# Power_Supply.net
KiCad netlist of a schematic drawn in EAGLE
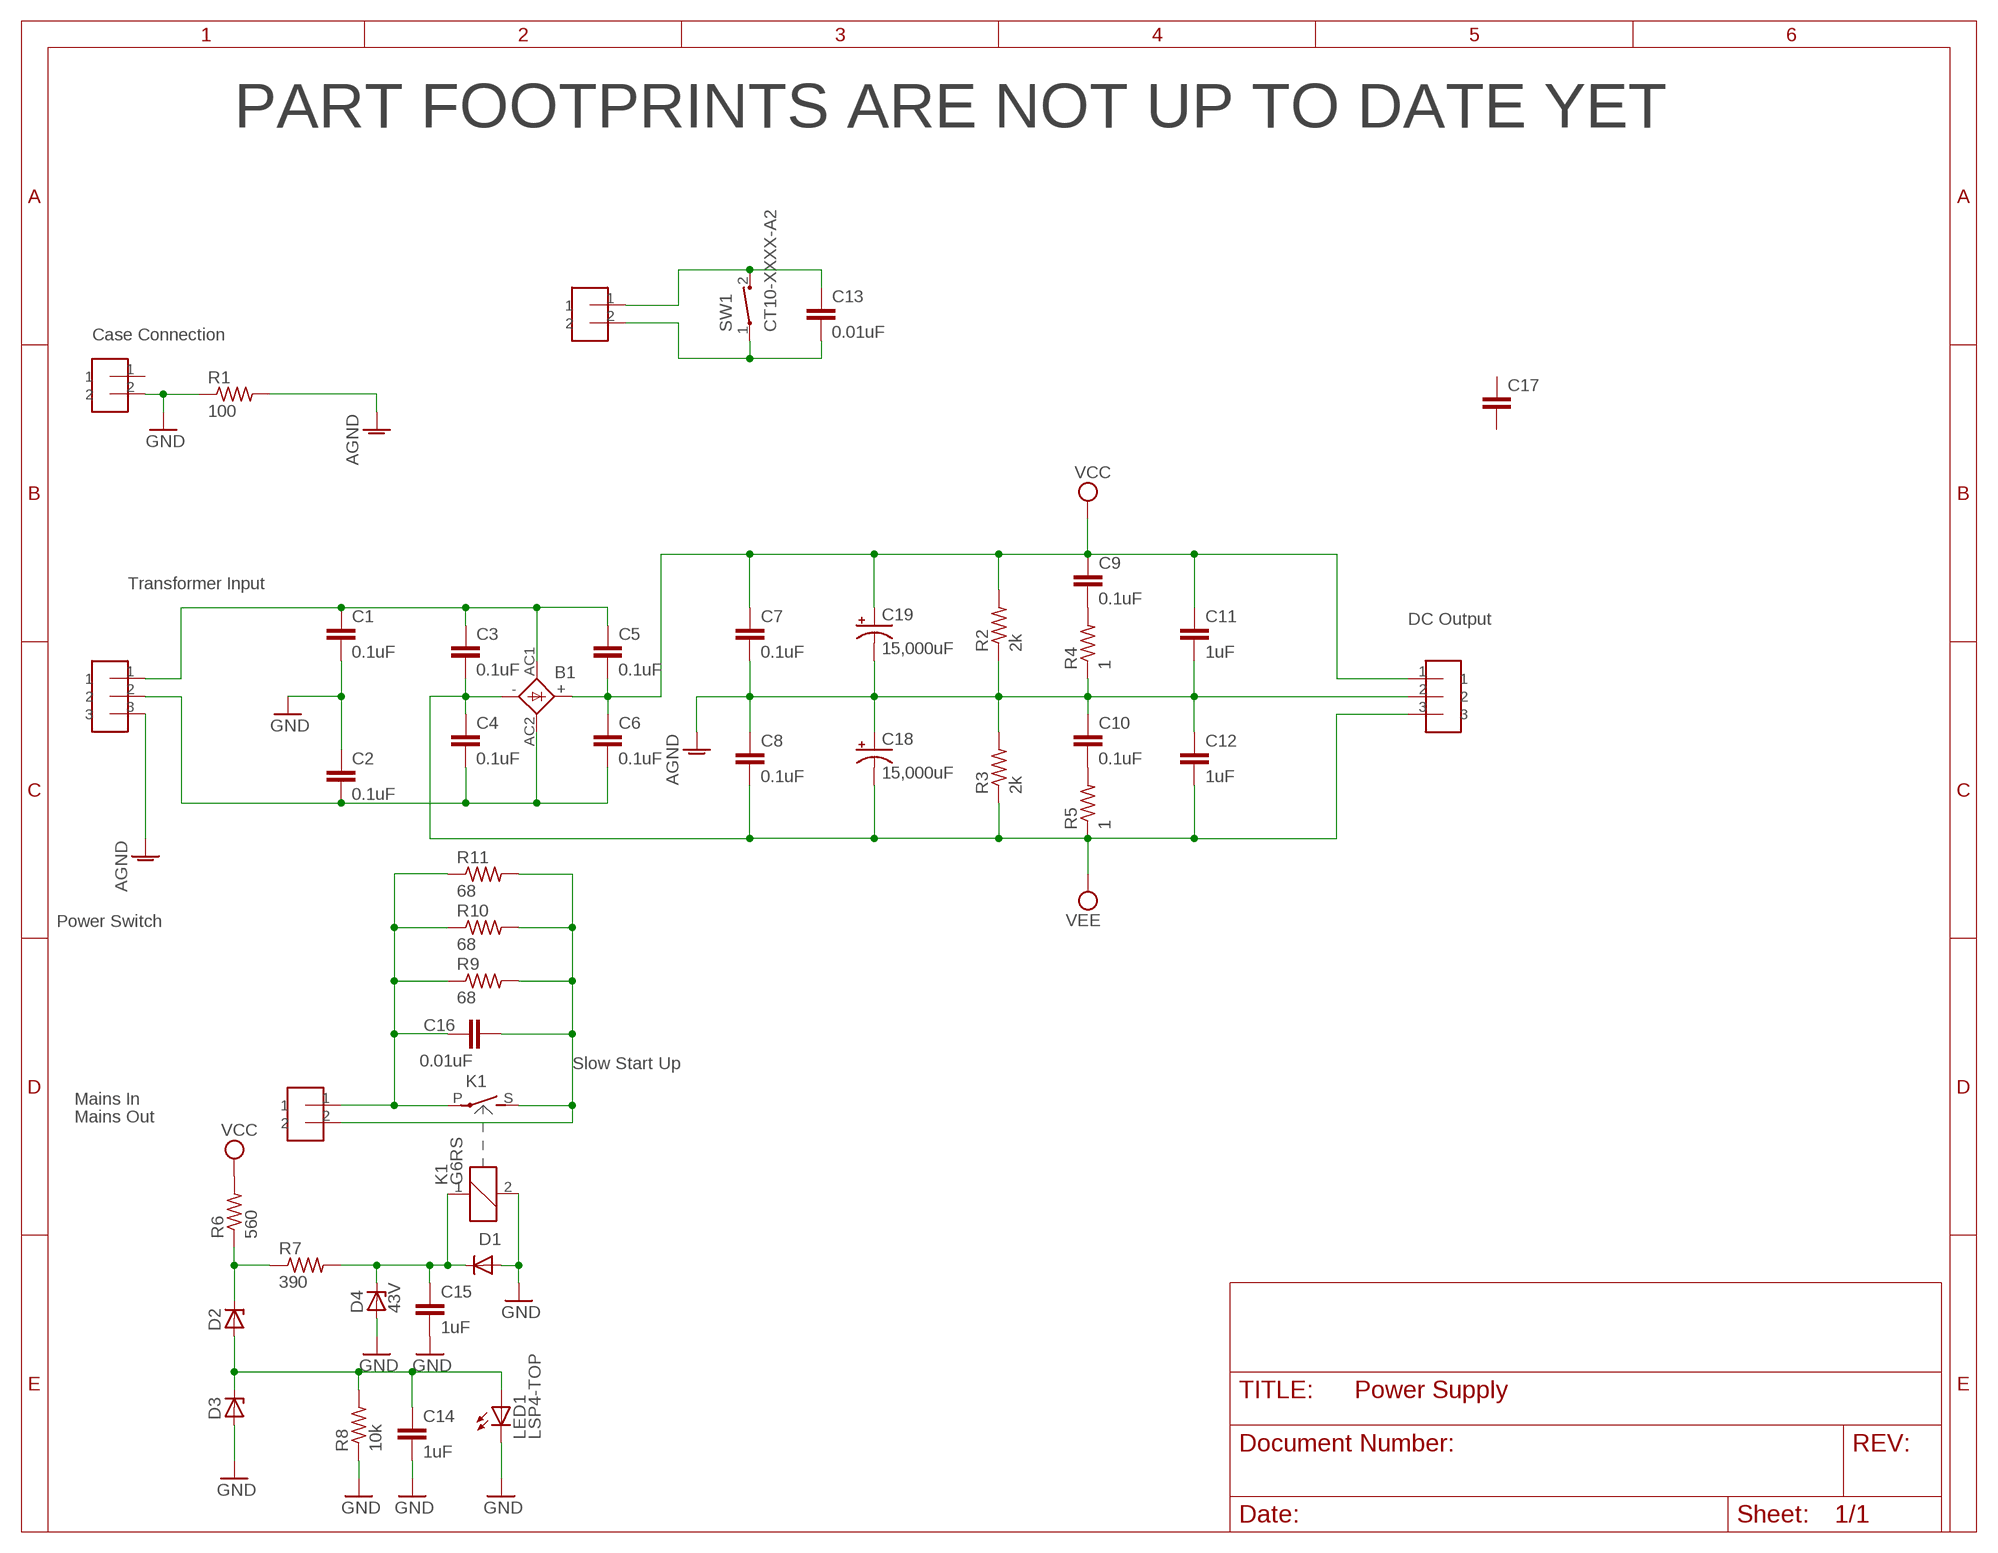
[diagram p0: schematic, sheet 1]

(export (version "E")
  (design (tool "Eeschema 10.0.6"))
  (components
    (comp (ref "B1")
      (value "GBPC1")
      (footprint "eagle-import:GBPC1")
      (libsource (lib "eagle-import") (part "GBPC1"))
    )
    (comp (ref "C1")
      (value "0.1uF")
      (footprint "eagle-import:C025-060X050")
      (libsource (lib "eagle-import") (part "C-EU025-060X050"))
    )
    (comp (ref "C2")
      (value "0.1uF")
      (footprint "eagle-import:C025-060X050")
      (libsource (lib "eagle-import") (part "C-EU025-060X050"))
    )
    (comp (ref "C3")
      (value "0.1uF")
      (footprint "eagle-import:C025-060X050")
      (libsource (lib "eagle-import") (part "C-EU025-060X050"))
    )
    (comp (ref "C4")
      (value "0.1uF")
      (footprint "eagle-import:C025-060X050")
      (libsource (lib "eagle-import") (part "C-EU025-060X050"))
    )
    (comp (ref "C5")
      (value "0.1uF")
      (footprint "eagle-import:C025-060X050")
      (libsource (lib "eagle-import") (part "C-EU025-060X050"))
    )
    (comp (ref "C6")
      (value "0.1uF")
      (footprint "eagle-import:C025-060X050")
      (libsource (lib "eagle-import") (part "C-EU025-060X050"))
    )
    (comp (ref "C7")
      (value "0.1uF")
      (footprint "eagle-import:C025-060X050")
      (libsource (lib "eagle-import") (part "C-EU025-060X050"))
    )
    (comp (ref "C8")
      (value "0.1uF")
      (footprint "eagle-import:C025-060X050")
      (libsource (lib "eagle-import") (part "C-EU025-060X050"))
    )
    (comp (ref "C9")
      (value "0.1uF")
      (footprint "eagle-import:C025-060X050")
      (libsource (lib "eagle-import") (part "C-EU025-060X050"))
    )
    (comp (ref "C10")
      (value "0.1uF")
      (footprint "eagle-import:C025-060X050")
      (libsource (lib "eagle-import") (part "C-EU025-060X050"))
    )
    (comp (ref "C11")
      (value "1uF")
      (footprint "eagle-import:C025-060X050")
      (libsource (lib "eagle-import") (part "C-EU025-060X050"))
    )
    (comp (ref "C12")
      (value "1uF")
      (footprint "eagle-import:C025-060X050")
      (libsource (lib "eagle-import") (part "C-EU025-060X050"))
    )
    (comp (ref "C13")
      (value "0.01uF")
      (footprint "eagle-import:C025-060X050")
      (libsource (lib "eagle-import") (part "C-EU025-060X050"))
    )
    (comp (ref "C14")
      (value "1uF")
      (footprint "eagle-import:C025-060X050")
      (libsource (lib "eagle-import") (part "C-EU025-060X050"))
    )
    (comp (ref "C15")
      (value "1uF")
      (footprint "eagle-import:C025-060X050")
      (libsource (lib "eagle-import") (part "C-EU025-060X050"))
    )
    (comp (ref "C16")
      (value "0.01uF")
      (footprint "eagle-import:C025-060X050")
      (libsource (lib "eagle-import") (part "C-EU025-060X050"))
    )
    (comp (ref "C17")
      (value "C-EU025-060X050")
      (footprint "eagle-import:C025-060X050")
      (libsource (lib "eagle-import") (part "C-EU025-060X050"))
    )
    (comp (ref "C18")
      (value "15,000uF")
      (footprint "eagle-import:E7,5-16")
      (libsource (lib "eagle-import") (part "CPOL-USE7.5-16"))
    )
    (comp (ref "C19")
      (value "15,000uF")
      (footprint "eagle-import:E7,5-16")
      (libsource (lib "eagle-import") (part "CPOL-USE7.5-16"))
    )
    (comp (ref "D1")
      (value "1N4004")
      (footprint "eagle-import:DO41-10")
      (libsource (lib "eagle-import") (part "1N4004"))
    )
    (comp (ref "D2")
      (value "ZENER-DIODEDO34-7")
      (footprint "eagle-import:DO34Z7")
      (libsource (lib "eagle-import") (part "ZENER-DIODEDO34-7"))
    )
    (comp (ref "D3")
      (value "ZENER-DIODEDO34-7")
      (footprint "eagle-import:DO34Z7")
      (libsource (lib "eagle-import") (part "ZENER-DIODEDO34-7"))
    )
    (comp (ref "D4")
      (value "43V")
      (footprint "eagle-import:DO34Z7")
      (libsource (lib "eagle-import") (part "ZENER-DIODEDO34-7"))
    )
    (comp (ref "K1")
      (value "G6RS")
      (footprint "eagle-import:G6RS")
      (libsource (lib "eagle-import") (part "G6RS"))
    )
    (comp (ref "LED1")
      (value "LSP4-TOP")
      (footprint "eagle-import:P47F-TOP")
      (libsource (lib "eagle-import") (part "P4-TOPLS"))
    )
    (comp (ref "R1")
      (value "100")
      (footprint "eagle-import:0617_22")
      (libsource (lib "eagle-import") (part "R-US_0617/22"))
    )
    (comp (ref "R2")
      (value "2k")
      (footprint "eagle-import:0617_22")
      (libsource (lib "eagle-import") (part "R-US_0617/22"))
    )
    (comp (ref "R3")
      (value "2k")
      (footprint "eagle-import:0617_22")
      (libsource (lib "eagle-import") (part "R-US_0617/22"))
    )
    (comp (ref "R4")
      (value "1")
      (footprint "eagle-import:0617_22")
      (libsource (lib "eagle-import") (part "R-US_0617/22"))
    )
    (comp (ref "R5")
      (value "1")
      (footprint "eagle-import:0617_22")
      (libsource (lib "eagle-import") (part "R-US_0617/22"))
    )
    (comp (ref "R6")
      (value "560")
      (footprint "eagle-import:0617_22")
      (libsource (lib "eagle-import") (part "R-US_0617/22"))
    )
    (comp (ref "R7")
      (value "390")
      (footprint "eagle-import:0617_22")
      (libsource (lib "eagle-import") (part "R-US_0617/22"))
    )
    (comp (ref "R8")
      (value "10k")
      (footprint "eagle-import:0617_22")
      (libsource (lib "eagle-import") (part "R-US_0617/22"))
    )
    (comp (ref "R9")
      (value "68")
      (footprint "eagle-import:0617_22")
      (libsource (lib "eagle-import") (part "R-US_0617/22"))
    )
    (comp (ref "R10")
      (value "68")
      (footprint "eagle-import:0617_22")
      (libsource (lib "eagle-import") (part "R-US_0617/22"))
    )
    (comp (ref "R11")
      (value "68")
      (footprint "eagle-import:0617_22")
      (libsource (lib "eagle-import") (part "R-US_0617/22"))
    )
    (comp (ref "SW1")
      (value "CT10-XXXX-A2")
      (footprint "eagle-import:CT10-XXXX-A2")
      (libsource (lib "eagle-import") (part "CT10-XXXX-A2"))
    )
    (comp (ref "U$1")
      (value "1X3HEADER_100MIL")
      (footprint "eagle-import:1X3_100MIL")
      (libsource (lib "eagle-import") (part "1X3HEADER_100MIL"))
    )
    (comp (ref "U$2")
      (value "1X3HEADER_100MIL")
      (footprint "eagle-import:1X3_100MIL")
      (libsource (lib "eagle-import") (part "1X3HEADER_100MIL"))
    )
    (comp (ref "U$3")
      (value "1X2HEADER_100MIL")
      (footprint "eagle-import:1X2_100MIL")
      (libsource (lib "eagle-import") (part "1X2HEADER_100MIL"))
    )
    (comp (ref "U$4")
      (value "1X2HEADER_100MIL")
      (footprint "eagle-import:1X2_100MIL")
      (libsource (lib "eagle-import") (part "1X2HEADER_100MIL"))
    )
    (comp (ref "U$5")
      (value "1X2HEADER_100MIL")
      (footprint "eagle-import:1X2_100MIL")
      (libsource (lib "eagle-import") (part "1X2HEADER_100MIL"))
    )
  )
  (nets
    (net (code "1") (name "AGND") (class "Default")
      (node (ref "C10") (pin "1") (pinfunction "1_1") (pintype "passive"))
      (node (ref "C11") (pin "2") (pinfunction "2_2") (pintype "passive"))
      (node (ref "C12") (pin "1") (pinfunction "1_1") (pintype "passive"))
      (node (ref "C18") (pin "+") (pinfunction "+_+") (pintype "passive"))
      (node (ref "C19") (pin "-") (pinfunction "-_-") (pintype "passive"))
      (node (ref "C7") (pin "2") (pinfunction "2_2") (pintype "passive"))
      (node (ref "C8") (pin "1") (pinfunction "1_1") (pintype "passive"))
      (node (ref "R1") (pin "2") (pinfunction "2_2") (pintype "passive"))
      (node (ref "R2") (pin "1") (pinfunction "1_1") (pintype "passive"))
      (node (ref "R3") (pin "2") (pinfunction "2_2") (pintype "passive"))
      (node (ref "R4") (pin "1") (pinfunction "1_1") (pintype "passive"))
      (node (ref "U$1") (pin "3") (pinfunction "3_3") (pintype "bidirectional"))
      (node (ref "U$2") (pin "2") (pinfunction "2_2") (pintype "bidirectional"))
    )
    (net (code "2") (name "GND") (class "Default")
      (node (ref "C1") (pin "2") (pinfunction "2_2") (pintype "passive"))
      (node (ref "C14") (pin "2") (pinfunction "2_2") (pintype "passive"))
      (node (ref "C15") (pin "2") (pinfunction "2_2") (pintype "passive"))
      (node (ref "C2") (pin "1") (pinfunction "1_1") (pintype "passive"))
      (node (ref "D1") (pin "A") (pinfunction "A_A") (pintype "passive"))
      (node (ref "D3") (pin "A") (pinfunction "A_A") (pintype "passive"))
      (node (ref "D4") (pin "A") (pinfunction "A_A") (pintype "passive"))
      (node (ref "K1") (pin "2") (pinfunction "2_2") (pintype "passive"))
      (node (ref "LED1") (pin "C") (pinfunction "C_C") (pintype "passive"))
      (node (ref "R1") (pin "1") (pinfunction "1_1") (pintype "passive"))
      (node (ref "R8") (pin "1") (pinfunction "1_1") (pintype "passive"))
      (node (ref "U$3") (pin "2") (pinfunction "2_2") (pintype "bidirectional"))
    )
    (net (code "3") (name "Net-(B1-PadAC1)") (class "Default")
      (node (ref "B1") (pin "AC1") (pinfunction "AC1_AC1") (pintype "passive"))
      (node (ref "C1") (pin "1") (pinfunction "1_1") (pintype "passive"))
      (node (ref "C3") (pin "1") (pinfunction "1_1") (pintype "passive"))
      (node (ref "C5") (pin "1") (pinfunction "1_1") (pintype "passive"))
      (node (ref "U$1") (pin "1") (pinfunction "1_1") (pintype "bidirectional"))
    )
    (net (code "4") (name "Net-(B1-PadAC2)") (class "Default")
      (node (ref "B1") (pin "AC2") (pinfunction "AC2_AC2") (pintype "passive"))
      (node (ref "C2") (pin "2") (pinfunction "2_2") (pintype "passive"))
      (node (ref "C4") (pin "2") (pinfunction "2_2") (pintype "passive"))
      (node (ref "C6") (pin "2") (pinfunction "2_2") (pintype "passive"))
      (node (ref "U$1") (pin "2") (pinfunction "2_2") (pintype "bidirectional"))
    )
    (net (code "5") (name "Net-(C9-Pad2)") (class "Default")
      (node (ref "C9") (pin "2") (pinfunction "2_2") (pintype "passive"))
      (node (ref "R4") (pin "2") (pinfunction "2_2") (pintype "passive"))
    )
    (net (code "6") (name "Net-(C10-Pad2)") (class "Default")
      (node (ref "C10") (pin "2") (pinfunction "2_2") (pintype "passive"))
      (node (ref "R5") (pin "2") (pinfunction "2_2") (pintype "passive"))
    )
    (net (code "7") (name "Net-(C13-Pad1)") (class "Default")
      (node (ref "C13") (pin "1") (pinfunction "1_1") (pintype "passive"))
      (node (ref "SW1") (pin "2") (pinfunction "2_2") (pintype "passive"))
      (node (ref "U$5") (pin "1") (pinfunction "1_1") (pintype "bidirectional"))
    )
    (net (code "8") (name "Net-(C13-Pad2)") (class "Default")
      (node (ref "C13") (pin "2") (pinfunction "2_2") (pintype "passive"))
      (node (ref "SW1") (pin "1") (pinfunction "1_1") (pintype "passive"))
      (node (ref "U$5") (pin "2") (pinfunction "2_2") (pintype "bidirectional"))
    )
    (net (code "9") (name "Net-(C14-Pad1)") (class "Default")
      (node (ref "C14") (pin "1") (pinfunction "1_1") (pintype "passive"))
      (node (ref "D2") (pin "A") (pinfunction "A_A") (pintype "passive"))
      (node (ref "D3") (pin "C") (pinfunction "C_C") (pintype "passive"))
      (node (ref "LED1") (pin "A") (pinfunction "A_A") (pintype "passive"))
      (node (ref "R8") (pin "2") (pinfunction "2_2") (pintype "passive"))
    )
    (net (code "10") (name "Net-(C15-Pad1)") (class "Default")
      (node (ref "C15") (pin "1") (pinfunction "1_1") (pintype "passive"))
      (node (ref "D1") (pin "C") (pinfunction "C_C") (pintype "passive"))
      (node (ref "D4") (pin "C") (pinfunction "C_C") (pintype "passive"))
      (node (ref "K1") (pin "1") (pinfunction "1_1") (pintype "passive"))
      (node (ref "R7") (pin "2") (pinfunction "2_2") (pintype "passive"))
    )
    (net (code "11") (name "Net-(C16-Pad1)") (class "Default")
      (node (ref "C16") (pin "1") (pinfunction "1_1") (pintype "passive"))
      (node (ref "K1") (pin "P") (pinfunction "P_P") (pintype "passive"))
      (node (ref "R10") (pin "1") (pinfunction "1_1") (pintype "passive"))
      (node (ref "R11") (pin "1") (pinfunction "1_1") (pintype "passive"))
      (node (ref "R9") (pin "1") (pinfunction "1_1") (pintype "passive"))
      (node (ref "U$4") (pin "1") (pinfunction "1_1") (pintype "bidirectional"))
    )
    (net (code "12") (name "Net-(C16-Pad2)") (class "Default")
      (node (ref "C16") (pin "2") (pinfunction "2_2") (pintype "passive"))
      (node (ref "K1") (pin "S") (pinfunction "S_S") (pintype "passive"))
      (node (ref "R10") (pin "2") (pinfunction "2_2") (pintype "passive"))
      (node (ref "R11") (pin "2") (pinfunction "2_2") (pintype "passive"))
      (node (ref "R9") (pin "2") (pinfunction "2_2") (pintype "passive"))
      (node (ref "U$4") (pin "2") (pinfunction "2_2") (pintype "bidirectional"))
    )
    (net (code "13") (name "Net-(D2-PadC)") (class "Default")
      (node (ref "D2") (pin "C") (pinfunction "C_C") (pintype "passive"))
      (node (ref "R6") (pin "1") (pinfunction "1_1") (pintype "passive"))
      (node (ref "R7") (pin "1") (pinfunction "1_1") (pintype "passive"))
    )
    (net (code "14") (name "VCC") (class "Default")
      (node (ref "B1") (pin "+") (pinfunction "+_+") (pintype "passive"))
      (node (ref "C11") (pin "1") (pinfunction "1_1") (pintype "passive"))
      (node (ref "C19") (pin "+") (pinfunction "+_+") (pintype "passive"))
      (node (ref "C5") (pin "2") (pinfunction "2_2") (pintype "passive"))
      (node (ref "C6") (pin "1") (pinfunction "1_1") (pintype "passive"))
      (node (ref "C7") (pin "1") (pinfunction "1_1") (pintype "passive"))
      (node (ref "C9") (pin "1") (pinfunction "1_1") (pintype "passive"))
      (node (ref "R2") (pin "2") (pinfunction "2_2") (pintype "passive"))
      (node (ref "R6") (pin "2") (pinfunction "2_2") (pintype "passive"))
      (node (ref "U$2") (pin "1") (pinfunction "1_1") (pintype "bidirectional"))
    )
    (net (code "15") (name "VEE") (class "Default")
      (node (ref "B1") (pin "-") (pinfunction "-_-") (pintype "passive"))
      (node (ref "C12") (pin "2") (pinfunction "2_2") (pintype "passive"))
      (node (ref "C18") (pin "-") (pinfunction "-_-") (pintype "passive"))
      (node (ref "C3") (pin "2") (pinfunction "2_2") (pintype "passive"))
      (node (ref "C4") (pin "1") (pinfunction "1_1") (pintype "passive"))
      (node (ref "C8") (pin "2") (pinfunction "2_2") (pintype "passive"))
      (node (ref "R3") (pin "1") (pinfunction "1_1") (pintype "passive"))
      (node (ref "R5") (pin "1") (pinfunction "1_1") (pintype "passive"))
      (node (ref "U$2") (pin "3") (pinfunction "3_3") (pintype "bidirectional"))
    )
    (net (code "16") (name "unconnected-(C17-Pad1)") (class "Default")
      (node (ref "C17") (pin "1") (pinfunction "1_1") (pintype "passive"))
    )
    (net (code "17") (name "unconnected-(C17-Pad2)") (class "Default")
      (node (ref "C17") (pin "2") (pinfunction "2_2") (pintype "passive"))
    )
    (net (code "18") (name "unconnected-(U$3-Pad1)") (class "Default")
      (node (ref "U$3") (pin "1") (pinfunction "1_1") (pintype "bidirectional"))
    )
  )
)
